# PGTNX01_teensy.net
KiCad netlist of a schematic drawn in EAGLE
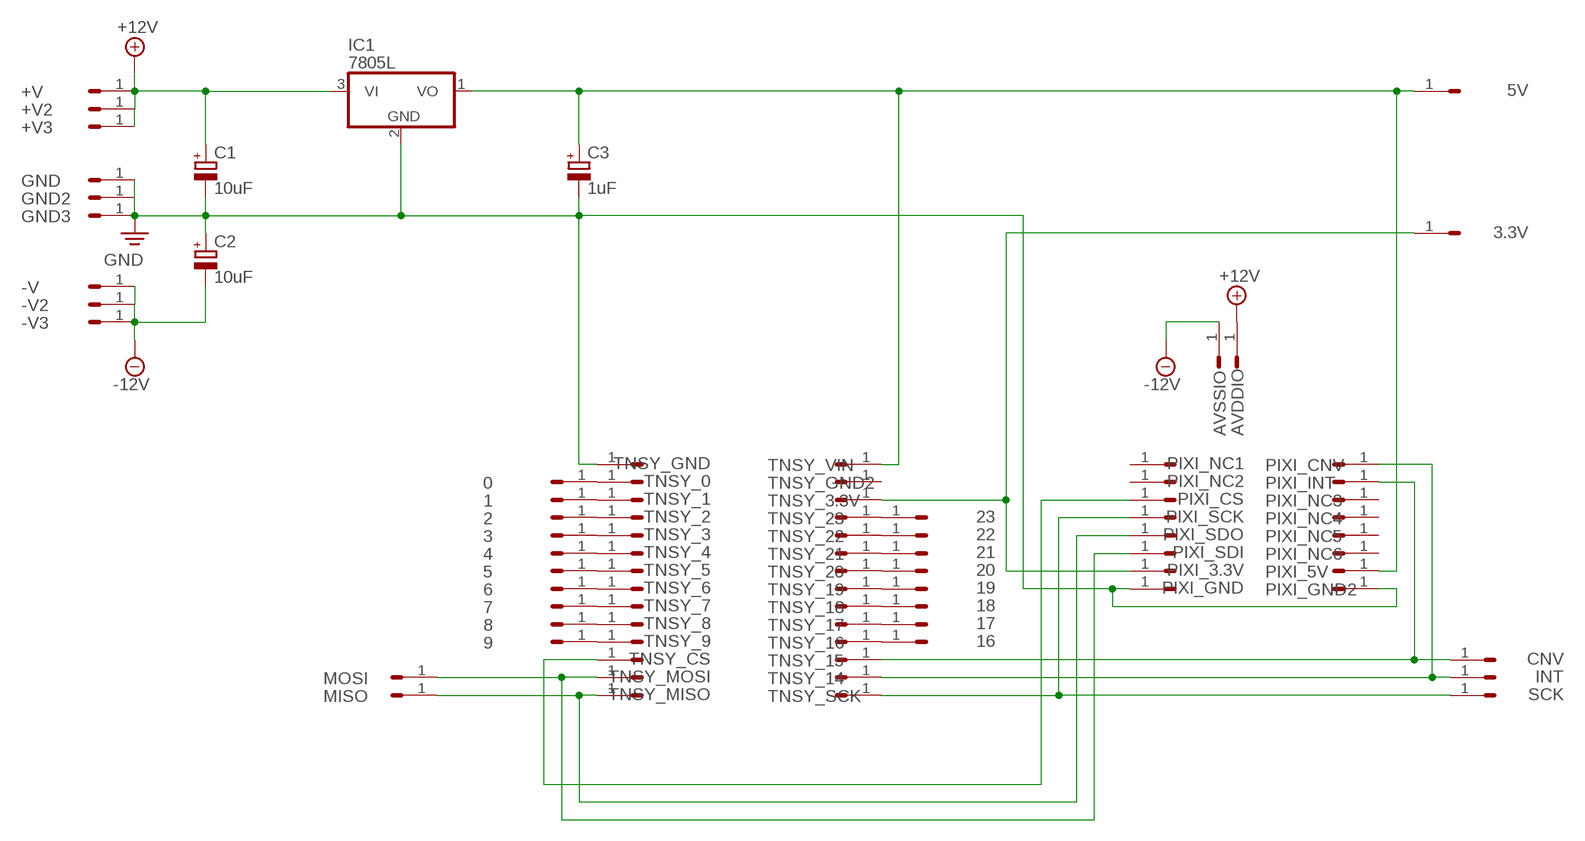
[diagram p0: schematic, sheet 1]

(export (version "E")
  (design (tool "Eeschema 10.0.6"))
  (components
    (comp (ref "+V")
      (value "HEADER/MALE/01")
      (footprint "eagle-import:HEADER_MALE_01")
      (fields (field (name "SPICEPREFIX") "X"))
      (libsource (lib "eagle-import") (part "HEADER/MALE/01"))
    )
    (comp (ref "+V2")
      (value "HEADER/MALE/01")
      (footprint "eagle-import:HEADER_MALE_01")
      (fields (field (name "SPICEPREFIX") "X"))
      (libsource (lib "eagle-import") (part "HEADER/MALE/01"))
    )
    (comp (ref "+V3")
      (value "HEADER/MALE/01")
      (footprint "eagle-import:HEADER_MALE_01")
      (fields (field (name "SPICEPREFIX") "X"))
      (libsource (lib "eagle-import") (part "HEADER/MALE/01"))
    )
    (comp (ref "-V")
      (value "HEADER/MALE/01")
      (footprint "eagle-import:HEADER_MALE_01")
      (fields (field (name "SPICEPREFIX") "X"))
      (libsource (lib "eagle-import") (part "HEADER/MALE/01"))
    )
    (comp (ref "-V2")
      (value "HEADER/MALE/01")
      (footprint "eagle-import:HEADER_MALE_01")
      (fields (field (name "SPICEPREFIX") "X"))
      (libsource (lib "eagle-import") (part "HEADER/MALE/01"))
    )
    (comp (ref "-V3")
      (value "HEADER/MALE/01")
      (footprint "eagle-import:HEADER_MALE_01")
      (fields (field (name "SPICEPREFIX") "X"))
      (libsource (lib "eagle-import") (part "HEADER/MALE/01"))
    )
    (comp (ref "0")
      (value "HEADER/MALE/01")
      (footprint "eagle-import:HEADER_MALE_01")
      (fields (field (name "SPICEPREFIX") "X"))
      (libsource (lib "eagle-import") (part "HEADER/MALE/01"))
    )
    (comp (ref "1")
      (value "HEADER/MALE/01")
      (footprint "eagle-import:HEADER_MALE_01")
      (fields (field (name "SPICEPREFIX") "X"))
      (libsource (lib "eagle-import") (part "HEADER/MALE/01"))
    )
    (comp (ref "2")
      (value "HEADER/MALE/01")
      (footprint "eagle-import:HEADER_MALE_01")
      (fields (field (name "SPICEPREFIX") "X"))
      (libsource (lib "eagle-import") (part "HEADER/MALE/01"))
    )
    (comp (ref "3")
      (value "HEADER/MALE/01")
      (footprint "eagle-import:HEADER_MALE_01")
      (fields (field (name "SPICEPREFIX") "X"))
      (libsource (lib "eagle-import") (part "HEADER/MALE/01"))
    )
    (comp (ref "3.3V")
      (value "HEADER/MALE/01")
      (footprint "eagle-import:HEADER_MALE_01")
      (fields (field (name "SPICEPREFIX") "X"))
      (libsource (lib "eagle-import") (part "HEADER/MALE/01"))
    )
    (comp (ref "4")
      (value "HEADER/MALE/01")
      (footprint "eagle-import:HEADER_MALE_01")
      (fields (field (name "SPICEPREFIX") "X"))
      (libsource (lib "eagle-import") (part "HEADER/MALE/01"))
    )
    (comp (ref "5")
      (value "HEADER/MALE/01")
      (footprint "eagle-import:HEADER_MALE_01")
      (fields (field (name "SPICEPREFIX") "X"))
      (libsource (lib "eagle-import") (part "HEADER/MALE/01"))
    )
    (comp (ref "5V")
      (value "HEADER/MALE/01")
      (footprint "eagle-import:HEADER_MALE_01")
      (fields (field (name "SPICEPREFIX") "X"))
      (libsource (lib "eagle-import") (part "HEADER/MALE/01"))
    )
    (comp (ref "6")
      (value "HEADER/MALE/01")
      (footprint "eagle-import:HEADER_MALE_01")
      (fields (field (name "SPICEPREFIX") "X"))
      (libsource (lib "eagle-import") (part "HEADER/MALE/01"))
    )
    (comp (ref "7")
      (value "HEADER/MALE/01")
      (footprint "eagle-import:HEADER_MALE_01")
      (fields (field (name "SPICEPREFIX") "X"))
      (libsource (lib "eagle-import") (part "HEADER/MALE/01"))
    )
    (comp (ref "8")
      (value "HEADER/MALE/01")
      (footprint "eagle-import:HEADER_MALE_01")
      (fields (field (name "SPICEPREFIX") "X"))
      (libsource (lib "eagle-import") (part "HEADER/MALE/01"))
    )
    (comp (ref "9")
      (value "HEADER/MALE/01")
      (footprint "eagle-import:HEADER_MALE_01")
      (fields (field (name "SPICEPREFIX") "X"))
      (libsource (lib "eagle-import") (part "HEADER/MALE/01"))
    )
    (comp (ref "16")
      (value "HEADER/MALE/01")
      (footprint "eagle-import:HEADER_MALE_01")
      (fields (field (name "SPICEPREFIX") "X"))
      (libsource (lib "eagle-import") (part "HEADER/MALE/01"))
    )
    (comp (ref "17")
      (value "HEADER/MALE/01")
      (footprint "eagle-import:HEADER_MALE_01")
      (fields (field (name "SPICEPREFIX") "X"))
      (libsource (lib "eagle-import") (part "HEADER/MALE/01"))
    )
    (comp (ref "18")
      (value "HEADER/MALE/01")
      (footprint "eagle-import:HEADER_MALE_01")
      (fields (field (name "SPICEPREFIX") "X"))
      (libsource (lib "eagle-import") (part "HEADER/MALE/01"))
    )
    (comp (ref "19")
      (value "HEADER/MALE/01")
      (footprint "eagle-import:HEADER_MALE_01")
      (fields (field (name "SPICEPREFIX") "X"))
      (libsource (lib "eagle-import") (part "HEADER/MALE/01"))
    )
    (comp (ref "20")
      (value "HEADER/MALE/01")
      (footprint "eagle-import:HEADER_MALE_01")
      (fields (field (name "SPICEPREFIX") "X"))
      (libsource (lib "eagle-import") (part "HEADER/MALE/01"))
    )
    (comp (ref "21")
      (value "HEADER/MALE/01")
      (footprint "eagle-import:HEADER_MALE_01")
      (fields (field (name "SPICEPREFIX") "X"))
      (libsource (lib "eagle-import") (part "HEADER/MALE/01"))
    )
    (comp (ref "22")
      (value "HEADER/MALE/01")
      (footprint "eagle-import:HEADER_MALE_01")
      (fields (field (name "SPICEPREFIX") "X"))
      (libsource (lib "eagle-import") (part "HEADER/MALE/01"))
    )
    (comp (ref "23")
      (value "HEADER/MALE/01")
      (footprint "eagle-import:HEADER_MALE_01")
      (fields (field (name "SPICEPREFIX") "X"))
      (libsource (lib "eagle-import") (part "HEADER/MALE/01"))
    )
    (comp (ref "AVDDIO")
      (value "HEADER/MALE/01")
      (footprint "eagle-import:HEADER_MALE_01")
      (fields (field (name "SPICEPREFIX") "X"))
      (libsource (lib "eagle-import") (part "HEADER/MALE/01"))
    )
    (comp (ref "AVSSIO")
      (value "HEADER/MALE/01")
      (footprint "eagle-import:HEADER_MALE_01")
      (fields (field (name "SPICEPREFIX") "X"))
      (libsource (lib "eagle-import") (part "HEADER/MALE/01"))
    )
    (comp (ref "C1")
      (value "10uF")
      (footprint "eagle-import:E2,5-6")
      (fields (field (name "SPICEPREFIX") "C"))
      (libsource (lib "eagle-import") (part "CAPACITOR/POLARIZEDE2.5-6"))
    )
    (comp (ref "C2")
      (value "10uF")
      (footprint "eagle-import:E2,5-6")
      (fields (field (name "SPICEPREFIX") "C"))
      (libsource (lib "eagle-import") (part "CAPACITOR/POLARIZEDE2.5-6"))
    )
    (comp (ref "C3")
      (value "1uF")
      (footprint "eagle-import:E2,5-6")
      (fields (field (name "SPICEPREFIX") "C"))
      (libsource (lib "eagle-import") (part "CAPACITOR/POLARIZEDE2.5-6"))
    )
    (comp (ref "CNV")
      (value "HEADER/MALE/01")
      (footprint "eagle-import:HEADER_MALE_01")
      (fields (field (name "SPICEPREFIX") "X"))
      (libsource (lib "eagle-import") (part "HEADER/MALE/01"))
    )
    (comp (ref "GND")
      (value "HEADER/MALE/01")
      (footprint "eagle-import:HEADER_MALE_01")
      (fields (field (name "SPICEPREFIX") "X"))
      (libsource (lib "eagle-import") (part "HEADER/MALE/01"))
    )
    (comp (ref "GND2")
      (value "HEADER/MALE/01")
      (footprint "eagle-import:HEADER_MALE_01")
      (fields (field (name "SPICEPREFIX") "X"))
      (libsource (lib "eagle-import") (part "HEADER/MALE/01"))
    )
    (comp (ref "GND3")
      (value "HEADER/MALE/01")
      (footprint "eagle-import:HEADER_MALE_01")
      (fields (field (name "SPICEPREFIX") "X"))
      (libsource (lib "eagle-import") (part "HEADER/MALE/01"))
    )
    (comp (ref "IC1")
      (value "7805L")
      (footprint "eagle-import:TO92")
      (libsource (lib "eagle-import") (part "78L05"))
    )
    (comp (ref "INT")
      (value "HEADER/MALE/01")
      (footprint "eagle-import:HEADER_MALE_01")
      (fields (field (name "SPICEPREFIX") "X"))
      (libsource (lib "eagle-import") (part "HEADER/MALE/01"))
    )
    (comp (ref "MISO")
      (value "HEADER/MALE/01")
      (footprint "eagle-import:HEADER_MALE_01")
      (fields (field (name "SPICEPREFIX") "X"))
      (libsource (lib "eagle-import") (part "HEADER/MALE/01"))
    )
    (comp (ref "MOSI")
      (value "HEADER/MALE/01")
      (footprint "eagle-import:HEADER_MALE_01")
      (fields (field (name "SPICEPREFIX") "X"))
      (libsource (lib "eagle-import") (part "HEADER/MALE/01"))
    )
    (comp (ref "PIXI_3.3V")
      (value "HEADER/MALE/01")
      (footprint "eagle-import:HEADER_MALE_01")
      (fields (field (name "SPICEPREFIX") "X"))
      (libsource (lib "eagle-import") (part "HEADER/MALE/01"))
    )
    (comp (ref "PIXI_5V")
      (value "HEADER/MALE/01")
      (footprint "eagle-import:HEADER_MALE_01")
      (fields (field (name "SPICEPREFIX") "X"))
      (libsource (lib "eagle-import") (part "HEADER/MALE/01"))
    )
    (comp (ref "PIXI_CNV")
      (value "HEADER/MALE/01")
      (footprint "eagle-import:HEADER_MALE_01")
      (fields (field (name "SPICEPREFIX") "X"))
      (libsource (lib "eagle-import") (part "HEADER/MALE/01"))
    )
    (comp (ref "PIXI_CS")
      (value "HEADER/MALE/01")
      (footprint "eagle-import:HEADER_MALE_01")
      (fields (field (name "SPICEPREFIX") "X"))
      (libsource (lib "eagle-import") (part "HEADER/MALE/01"))
    )
    (comp (ref "PIXI_GND")
      (value "HEADER/MALE/01")
      (footprint "eagle-import:HEADER_MALE_01")
      (fields (field (name "SPICEPREFIX") "X"))
      (libsource (lib "eagle-import") (part "HEADER/MALE/01"))
    )
    (comp (ref "PIXI_GND2")
      (value "HEADER/MALE/01")
      (footprint "eagle-import:HEADER_MALE_01")
      (fields (field (name "SPICEPREFIX") "X"))
      (libsource (lib "eagle-import") (part "HEADER/MALE/01"))
    )
    (comp (ref "PIXI_INT")
      (value "HEADER/MALE/01")
      (footprint "eagle-import:HEADER_MALE_01")
      (fields (field (name "SPICEPREFIX") "X"))
      (libsource (lib "eagle-import") (part "HEADER/MALE/01"))
    )
    (comp (ref "PIXI_NC1")
      (value "HEADER/MALE/01")
      (footprint "eagle-import:HEADER_MALE_01")
      (fields (field (name "SPICEPREFIX") "X"))
      (libsource (lib "eagle-import") (part "HEADER/MALE/01"))
    )
    (comp (ref "PIXI_NC2")
      (value "HEADER/MALE/01")
      (footprint "eagle-import:HEADER_MALE_01")
      (fields (field (name "SPICEPREFIX") "X"))
      (libsource (lib "eagle-import") (part "HEADER/MALE/01"))
    )
    (comp (ref "PIXI_NC3")
      (value "HEADER/MALE/01")
      (footprint "eagle-import:HEADER_MALE_01")
      (fields (field (name "SPICEPREFIX") "X"))
      (libsource (lib "eagle-import") (part "HEADER/MALE/01"))
    )
    (comp (ref "PIXI_NC4")
      (value "HEADER/MALE/01")
      (footprint "eagle-import:HEADER_MALE_01")
      (fields (field (name "SPICEPREFIX") "X"))
      (libsource (lib "eagle-import") (part "HEADER/MALE/01"))
    )
    (comp (ref "PIXI_NC5")
      (value "HEADER/MALE/01")
      (footprint "eagle-import:HEADER_MALE_01")
      (fields (field (name "SPICEPREFIX") "X"))
      (libsource (lib "eagle-import") (part "HEADER/MALE/01"))
    )
    (comp (ref "PIXI_NC6")
      (value "HEADER/MALE/01")
      (footprint "eagle-import:HEADER_MALE_01")
      (fields (field (name "SPICEPREFIX") "X"))
      (libsource (lib "eagle-import") (part "HEADER/MALE/01"))
    )
    (comp (ref "PIXI_SCK")
      (value "HEADER/MALE/01")
      (footprint "eagle-import:HEADER_MALE_01")
      (fields (field (name "SPICEPREFIX") "X"))
      (libsource (lib "eagle-import") (part "HEADER/MALE/01"))
    )
    (comp (ref "PIXI_SDI")
      (value "HEADER/MALE/01")
      (footprint "eagle-import:HEADER_MALE_01")
      (fields (field (name "SPICEPREFIX") "X"))
      (libsource (lib "eagle-import") (part "HEADER/MALE/01"))
    )
    (comp (ref "PIXI_SDO")
      (value "HEADER/MALE/01")
      (footprint "eagle-import:HEADER_MALE_01")
      (fields (field (name "SPICEPREFIX") "X"))
      (libsource (lib "eagle-import") (part "HEADER/MALE/01"))
    )
    (comp (ref "SCK")
      (value "HEADER/MALE/01")
      (footprint "eagle-import:HEADER_MALE_01")
      (fields (field (name "SPICEPREFIX") "X"))
      (libsource (lib "eagle-import") (part "HEADER/MALE/01"))
    )
    (comp (ref "TNSY_0")
      (value "HEADER/MALE/01")
      (footprint "eagle-import:HEADER_MALE_01")
      (fields (field (name "SPICEPREFIX") "X"))
      (libsource (lib "eagle-import") (part "HEADER/MALE/01"))
    )
    (comp (ref "TNSY_1")
      (value "HEADER/MALE/01")
      (footprint "eagle-import:HEADER_MALE_01")
      (fields (field (name "SPICEPREFIX") "X"))
      (libsource (lib "eagle-import") (part "HEADER/MALE/01"))
    )
    (comp (ref "TNSY_2")
      (value "HEADER/MALE/01")
      (footprint "eagle-import:HEADER_MALE_01")
      (fields (field (name "SPICEPREFIX") "X"))
      (libsource (lib "eagle-import") (part "HEADER/MALE/01"))
    )
    (comp (ref "TNSY_3")
      (value "HEADER/MALE/01")
      (footprint "eagle-import:HEADER_MALE_01")
      (fields (field (name "SPICEPREFIX") "X"))
      (libsource (lib "eagle-import") (part "HEADER/MALE/01"))
    )
    (comp (ref "TNSY_3.3V")
      (value "HEADER/MALE/01")
      (footprint "eagle-import:HEADER_MALE_01")
      (fields (field (name "SPICEPREFIX") "X"))
      (libsource (lib "eagle-import") (part "HEADER/MALE/01"))
    )
    (comp (ref "TNSY_4")
      (value "HEADER/MALE/01")
      (footprint "eagle-import:HEADER_MALE_01")
      (fields (field (name "SPICEPREFIX") "X"))
      (libsource (lib "eagle-import") (part "HEADER/MALE/01"))
    )
    (comp (ref "TNSY_5")
      (value "HEADER/MALE/01")
      (footprint "eagle-import:HEADER_MALE_01")
      (fields (field (name "SPICEPREFIX") "X"))
      (libsource (lib "eagle-import") (part "HEADER/MALE/01"))
    )
    (comp (ref "TNSY_6")
      (value "HEADER/MALE/01")
      (footprint "eagle-import:HEADER_MALE_01")
      (fields (field (name "SPICEPREFIX") "X"))
      (libsource (lib "eagle-import") (part "HEADER/MALE/01"))
    )
    (comp (ref "TNSY_7")
      (value "HEADER/MALE/01")
      (footprint "eagle-import:HEADER_MALE_01")
      (fields (field (name "SPICEPREFIX") "X"))
      (libsource (lib "eagle-import") (part "HEADER/MALE/01"))
    )
    (comp (ref "TNSY_8")
      (value "HEADER/MALE/01")
      (footprint "eagle-import:HEADER_MALE_01")
      (fields (field (name "SPICEPREFIX") "X"))
      (libsource (lib "eagle-import") (part "HEADER/MALE/01"))
    )
    (comp (ref "TNSY_9")
      (value "HEADER/MALE/01")
      (footprint "eagle-import:HEADER_MALE_01")
      (fields (field (name "SPICEPREFIX") "X"))
      (libsource (lib "eagle-import") (part "HEADER/MALE/01"))
    )
    (comp (ref "TNSY_14")
      (value "HEADER/MALE/01")
      (footprint "eagle-import:HEADER_MALE_01")
      (fields (field (name "SPICEPREFIX") "X"))
      (libsource (lib "eagle-import") (part "HEADER/MALE/01"))
    )
    (comp (ref "TNSY_15")
      (value "HEADER/MALE/01")
      (footprint "eagle-import:HEADER_MALE_01")
      (fields (field (name "SPICEPREFIX") "X"))
      (libsource (lib "eagle-import") (part "HEADER/MALE/01"))
    )
    (comp (ref "TNSY_16")
      (value "HEADER/MALE/01")
      (footprint "eagle-import:HEADER_MALE_01")
      (fields (field (name "SPICEPREFIX") "X"))
      (libsource (lib "eagle-import") (part "HEADER/MALE/01"))
    )
    (comp (ref "TNSY_17")
      (value "HEADER/MALE/01")
      (footprint "eagle-import:HEADER_MALE_01")
      (fields (field (name "SPICEPREFIX") "X"))
      (libsource (lib "eagle-import") (part "HEADER/MALE/01"))
    )
    (comp (ref "TNSY_18")
      (value "HEADER/MALE/01")
      (footprint "eagle-import:HEADER_MALE_01")
      (fields (field (name "SPICEPREFIX") "X"))
      (libsource (lib "eagle-import") (part "HEADER/MALE/01"))
    )
    (comp (ref "TNSY_19")
      (value "HEADER/MALE/01")
      (footprint "eagle-import:HEADER_MALE_01")
      (fields (field (name "SPICEPREFIX") "X"))
      (libsource (lib "eagle-import") (part "HEADER/MALE/01"))
    )
    (comp (ref "TNSY_20")
      (value "HEADER/MALE/01")
      (footprint "eagle-import:HEADER_MALE_01")
      (fields (field (name "SPICEPREFIX") "X"))
      (libsource (lib "eagle-import") (part "HEADER/MALE/01"))
    )
    (comp (ref "TNSY_21")
      (value "HEADER/MALE/01")
      (footprint "eagle-import:HEADER_MALE_01")
      (fields (field (name "SPICEPREFIX") "X"))
      (libsource (lib "eagle-import") (part "HEADER/MALE/01"))
    )
    (comp (ref "TNSY_22")
      (value "HEADER/MALE/01")
      (footprint "eagle-import:HEADER_MALE_01")
      (fields (field (name "SPICEPREFIX") "X"))
      (libsource (lib "eagle-import") (part "HEADER/MALE/01"))
    )
    (comp (ref "TNSY_23")
      (value "HEADER/MALE/01")
      (footprint "eagle-import:HEADER_MALE_01")
      (fields (field (name "SPICEPREFIX") "X"))
      (libsource (lib "eagle-import") (part "HEADER/MALE/01"))
    )
    (comp (ref "TNSY_CS")
      (value "HEADER/MALE/01")
      (footprint "eagle-import:HEADER_MALE_01")
      (fields (field (name "SPICEPREFIX") "X"))
      (libsource (lib "eagle-import") (part "HEADER/MALE/01"))
    )
    (comp (ref "TNSY_GND")
      (value "HEADER/MALE/01")
      (footprint "eagle-import:HEADER_MALE_01")
      (fields (field (name "SPICEPREFIX") "X"))
      (libsource (lib "eagle-import") (part "HEADER/MALE/01"))
    )
    (comp (ref "TNSY_GND2")
      (value "HEADER/MALE/01")
      (footprint "eagle-import:HEADER_MALE_01")
      (fields (field (name "SPICEPREFIX") "X"))
      (libsource (lib "eagle-import") (part "HEADER/MALE/01"))
    )
    (comp (ref "TNSY_MISO")
      (value "HEADER/MALE/01")
      (footprint "eagle-import:HEADER_MALE_01")
      (fields (field (name "SPICEPREFIX") "X"))
      (libsource (lib "eagle-import") (part "HEADER/MALE/01"))
    )
    (comp (ref "TNSY_MOSI")
      (value "HEADER/MALE/01")
      (footprint "eagle-import:HEADER_MALE_01")
      (fields (field (name "SPICEPREFIX") "X"))
      (libsource (lib "eagle-import") (part "HEADER/MALE/01"))
    )
    (comp (ref "TNSY_SCK")
      (value "HEADER/MALE/01")
      (footprint "eagle-import:HEADER_MALE_01")
      (fields (field (name "SPICEPREFIX") "X"))
      (libsource (lib "eagle-import") (part "HEADER/MALE/01"))
    )
    (comp (ref "TNSY_VIN")
      (value "HEADER/MALE/01")
      (footprint "eagle-import:HEADER_MALE_01")
      (fields (field (name "SPICEPREFIX") "X"))
      (libsource (lib "eagle-import") (part "HEADER/MALE/01"))
    )
  )
  (nets
    (net (code "1") (name "+12V") (class "Default")
      (node (ref "+V") (pin "1") (pinfunction "3_1") (pintype "passive"))
      (node (ref "+V2") (pin "1") (pinfunction "3_1") (pintype "passive"))
      (node (ref "+V3") (pin "1") (pinfunction "3_1") (pintype "passive"))
      (node (ref "AVDDIO") (pin "1") (pinfunction "3_1") (pintype "passive"))
      (node (ref "C1") (pin "+") (pinfunction "+_+") (pintype "passive"))
      (node (ref "IC1") (pin "3") (pinfunction "VI_3") (pintype "input"))
    )
    (net (code "2") (name "-12V") (class "Default")
      (node (ref "-V") (pin "1") (pinfunction "3_1") (pintype "passive"))
      (node (ref "-V2") (pin "1") (pinfunction "3_1") (pintype "passive"))
      (node (ref "-V3") (pin "1") (pinfunction "3_1") (pintype "passive"))
      (node (ref "AVSSIO") (pin "1") (pinfunction "3_1") (pintype "passive"))
      (node (ref "C2") (pin "-") (pinfunction "-_-") (pintype "passive"))
    )
    (net (code "3") (name "GND") (class "Default")
      (node (ref "C1") (pin "-") (pinfunction "-_-") (pintype "passive"))
      (node (ref "C2") (pin "+") (pinfunction "+_+") (pintype "passive"))
      (node (ref "C3") (pin "-") (pinfunction "-_-") (pintype "passive"))
      (node (ref "GND") (pin "1") (pinfunction "3_1") (pintype "passive"))
      (node (ref "GND2") (pin "1") (pinfunction "3_1") (pintype "passive"))
      (node (ref "GND3") (pin "1") (pinfunction "3_1") (pintype "passive"))
      (node (ref "IC1") (pin "2") (pinfunction "GND_2") (pintype "passive"))
      (node (ref "PIXI_GND") (pin "1") (pinfunction "3_1") (pintype "passive"))
      (node (ref "PIXI_GND2") (pin "1") (pinfunction "3_1") (pintype "passive"))
      (node (ref "TNSY_GND") (pin "1") (pinfunction "3_1") (pintype "passive"))
    )
    (net (code "4") (name "Net-(0-3)") (class "Default")
      (node (ref "0") (pin "1") (pinfunction "3_1") (pintype "passive"))
      (node (ref "TNSY_0") (pin "1") (pinfunction "3_1") (pintype "passive"))
    )
    (net (code "5") (name "Net-(1-3)") (class "Default")
      (node (ref "1") (pin "1") (pinfunction "3_1") (pintype "passive"))
      (node (ref "TNSY_1") (pin "1") (pinfunction "3_1") (pintype "passive"))
    )
    (net (code "6") (name "Net-(2-3)") (class "Default")
      (node (ref "2") (pin "1") (pinfunction "3_1") (pintype "passive"))
      (node (ref "TNSY_2") (pin "1") (pinfunction "3_1") (pintype "passive"))
    )
    (net (code "7") (name "Net-(3-3)") (class "Default")
      (node (ref "3") (pin "1") (pinfunction "3_1") (pintype "passive"))
      (node (ref "TNSY_3") (pin "1") (pinfunction "3_1") (pintype "passive"))
    )
    (net (code "8") (name "Net-(3.3V-3)") (class "Default")
      (node (ref "3.3V") (pin "1") (pinfunction "3_1") (pintype "passive"))
      (node (ref "PIXI_3.3V") (pin "1") (pinfunction "3_1") (pintype "passive"))
      (node (ref "TNSY_3.3V") (pin "1") (pinfunction "3_1") (pintype "passive"))
    )
    (net (code "9") (name "Net-(4-3)") (class "Default")
      (node (ref "4") (pin "1") (pinfunction "3_1") (pintype "passive"))
      (node (ref "TNSY_4") (pin "1") (pinfunction "3_1") (pintype "passive"))
    )
    (net (code "10") (name "Net-(5-3)") (class "Default")
      (node (ref "5") (pin "1") (pinfunction "3_1") (pintype "passive"))
      (node (ref "TNSY_5") (pin "1") (pinfunction "3_1") (pintype "passive"))
    )
    (net (code "11") (name "Net-(5V-3)") (class "Default")
      (node (ref "5V") (pin "1") (pinfunction "3_1") (pintype "passive"))
      (node (ref "C3") (pin "+") (pinfunction "+_+") (pintype "passive"))
      (node (ref "IC1") (pin "1") (pinfunction "VO_1") (pintype "passive"))
      (node (ref "PIXI_5V") (pin "1") (pinfunction "3_1") (pintype "passive"))
      (node (ref "TNSY_VIN") (pin "1") (pinfunction "3_1") (pintype "passive"))
    )
    (net (code "12") (name "Net-(6-3)") (class "Default")
      (node (ref "6") (pin "1") (pinfunction "3_1") (pintype "passive"))
      (node (ref "TNSY_6") (pin "1") (pinfunction "3_1") (pintype "passive"))
    )
    (net (code "13") (name "Net-(7-3)") (class "Default")
      (node (ref "7") (pin "1") (pinfunction "3_1") (pintype "passive"))
      (node (ref "TNSY_7") (pin "1") (pinfunction "3_1") (pintype "passive"))
    )
    (net (code "14") (name "Net-(8-3)") (class "Default")
      (node (ref "8") (pin "1") (pinfunction "3_1") (pintype "passive"))
      (node (ref "TNSY_8") (pin "1") (pinfunction "3_1") (pintype "passive"))
    )
    (net (code "15") (name "Net-(9-3)") (class "Default")
      (node (ref "9") (pin "1") (pinfunction "3_1") (pintype "passive"))
      (node (ref "TNSY_9") (pin "1") (pinfunction "3_1") (pintype "passive"))
    )
    (net (code "16") (name "Net-(16-3)") (class "Default")
      (node (ref "16") (pin "1") (pinfunction "3_1") (pintype "passive"))
      (node (ref "TNSY_16") (pin "1") (pinfunction "3_1") (pintype "passive"))
    )
    (net (code "17") (name "Net-(17-3)") (class "Default")
      (node (ref "17") (pin "1") (pinfunction "3_1") (pintype "passive"))
      (node (ref "TNSY_17") (pin "1") (pinfunction "3_1") (pintype "passive"))
    )
    (net (code "18") (name "Net-(18-3)") (class "Default")
      (node (ref "18") (pin "1") (pinfunction "3_1") (pintype "passive"))
      (node (ref "TNSY_18") (pin "1") (pinfunction "3_1") (pintype "passive"))
    )
    (net (code "19") (name "Net-(19-3)") (class "Default")
      (node (ref "19") (pin "1") (pinfunction "3_1") (pintype "passive"))
      (node (ref "TNSY_19") (pin "1") (pinfunction "3_1") (pintype "passive"))
    )
    (net (code "20") (name "Net-(20-3)") (class "Default")
      (node (ref "20") (pin "1") (pinfunction "3_1") (pintype "passive"))
      (node (ref "TNSY_20") (pin "1") (pinfunction "3_1") (pintype "passive"))
    )
    (net (code "21") (name "Net-(21-3)") (class "Default")
      (node (ref "21") (pin "1") (pinfunction "3_1") (pintype "passive"))
      (node (ref "TNSY_21") (pin "1") (pinfunction "3_1") (pintype "passive"))
    )
    (net (code "22") (name "Net-(22-3)") (class "Default")
      (node (ref "22") (pin "1") (pinfunction "3_1") (pintype "passive"))
      (node (ref "TNSY_22") (pin "1") (pinfunction "3_1") (pintype "passive"))
    )
    (net (code "23") (name "Net-(23-3)") (class "Default")
      (node (ref "23") (pin "1") (pinfunction "3_1") (pintype "passive"))
      (node (ref "TNSY_23") (pin "1") (pinfunction "3_1") (pintype "passive"))
    )
    (net (code "24") (name "Net-(CNV-3)") (class "Default")
      (node (ref "CNV") (pin "1") (pinfunction "3_1") (pintype "passive"))
      (node (ref "PIXI_INT") (pin "1") (pinfunction "3_1") (pintype "passive"))
      (node (ref "TNSY_15") (pin "1") (pinfunction "3_1") (pintype "passive"))
    )
    (net (code "25") (name "Net-(INT-3)") (class "Default")
      (node (ref "INT") (pin "1") (pinfunction "3_1") (pintype "passive"))
      (node (ref "PIXI_CNV") (pin "1") (pinfunction "3_1") (pintype "passive"))
      (node (ref "TNSY_14") (pin "1") (pinfunction "3_1") (pintype "passive"))
    )
    (net (code "26") (name "Net-(MISO-3)") (class "Default")
      (node (ref "MISO") (pin "1") (pinfunction "3_1") (pintype "passive"))
      (node (ref "PIXI_SDO") (pin "1") (pinfunction "3_1") (pintype "passive"))
      (node (ref "TNSY_MISO") (pin "1") (pinfunction "3_1") (pintype "passive"))
    )
    (net (code "27") (name "Net-(MOSI-3)") (class "Default")
      (node (ref "MOSI") (pin "1") (pinfunction "3_1") (pintype "passive"))
      (node (ref "PIXI_SDI") (pin "1") (pinfunction "3_1") (pintype "passive"))
      (node (ref "TNSY_MOSI") (pin "1") (pinfunction "3_1") (pintype "passive"))
    )
    (net (code "28") (name "Net-(PIXI_CS-3)") (class "Default")
      (node (ref "PIXI_CS") (pin "1") (pinfunction "3_1") (pintype "passive"))
      (node (ref "TNSY_CS") (pin "1") (pinfunction "3_1") (pintype "passive"))
    )
    (net (code "29") (name "Net-(PIXI_SCK-3)") (class "Default")
      (node (ref "PIXI_SCK") (pin "1") (pinfunction "3_1") (pintype "passive"))
      (node (ref "SCK") (pin "1") (pinfunction "3_1") (pintype "passive"))
      (node (ref "TNSY_SCK") (pin "1") (pinfunction "3_1") (pintype "passive"))
    )
    (net (code "30") (name "unconnected-(PIXI_NC1-3-Pad1)") (class "Default")
      (node (ref "PIXI_NC1") (pin "1") (pinfunction "3_1") (pintype "passive"))
    )
    (net (code "31") (name "unconnected-(PIXI_NC2-3-Pad1)") (class "Default")
      (node (ref "PIXI_NC2") (pin "1") (pinfunction "3_1") (pintype "passive"))
    )
    (net (code "32") (name "unconnected-(PIXI_NC3-3-Pad1)") (class "Default")
      (node (ref "PIXI_NC3") (pin "1") (pinfunction "3_1") (pintype "passive"))
    )
    (net (code "33") (name "unconnected-(PIXI_NC4-3-Pad1)") (class "Default")
      (node (ref "PIXI_NC4") (pin "1") (pinfunction "3_1") (pintype "passive"))
    )
    (net (code "34") (name "unconnected-(PIXI_NC5-3-Pad1)") (class "Default")
      (node (ref "PIXI_NC5") (pin "1") (pinfunction "3_1") (pintype "passive"))
    )
    (net (code "35") (name "unconnected-(PIXI_NC6-3-Pad1)") (class "Default")
      (node (ref "PIXI_NC6") (pin "1") (pinfunction "3_1") (pintype "passive"))
    )
    (net (code "36") (name "unconnected-(TNSY_GND2-3-Pad1)") (class "Default")
      (node (ref "TNSY_GND2") (pin "1") (pinfunction "3_1") (pintype "passive"))
    )
  )
)
